# boilerplate.net
KiCad netlist of a schematic drawn in EAGLE
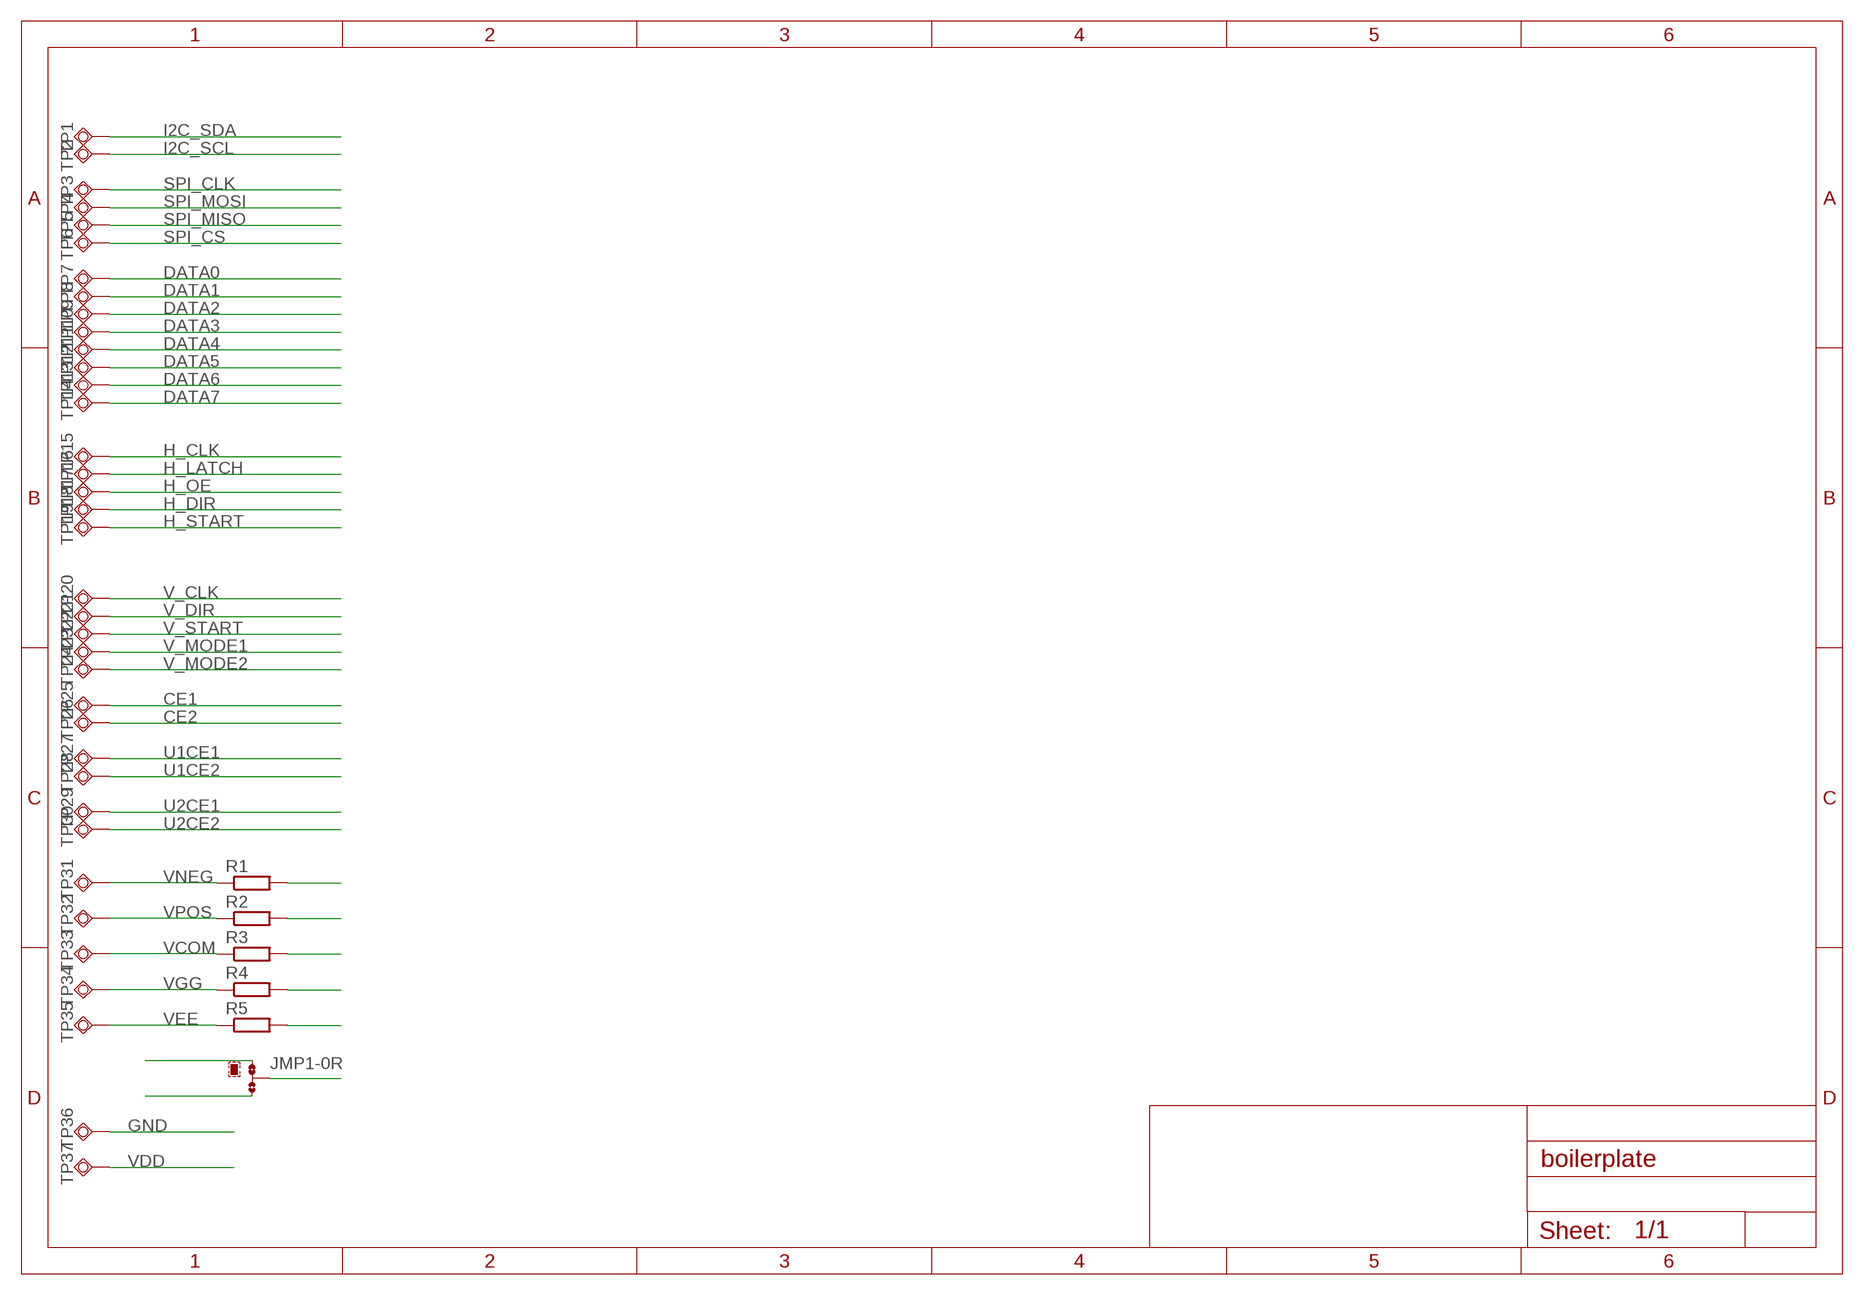
[diagram p0: schematic, sheet 1]

(export (version "E")
  (design (tool "Eeschema 10.0.6"))
  (components
    (comp (ref "JMP1")
      (value "0R-JUMPA")
      (footprint "eagle-import:A0R-JMP")
      (libsource (lib "eagle-import") (part "0R-JUMPA"))
    )
    (comp (ref "R1")
      (value "R-EU_R0805")
      (footprint "eagle-import:R0805")
      (libsource (lib "eagle-import") (part "R-EU_R0805"))
    )
    (comp (ref "R2")
      (value "R-EU_R0805")
      (footprint "eagle-import:R0805")
      (libsource (lib "eagle-import") (part "R-EU_R0805"))
    )
    (comp (ref "R3")
      (value "R-EU_R0805")
      (footprint "eagle-import:R0805")
      (libsource (lib "eagle-import") (part "R-EU_R0805"))
    )
    (comp (ref "R4")
      (value "R-EU_R0805")
      (footprint "eagle-import:R0805")
      (libsource (lib "eagle-import") (part "R-EU_R0805"))
    )
    (comp (ref "R5")
      (value "R-EU_R0805")
      (footprint "eagle-import:R0805")
      (libsource (lib "eagle-import") (part "R-EU_R0805"))
    )
    (comp (ref "TP1")
      (value "TESTPAD0.6")
      (footprint "eagle-import:VIA0.6")
      (libsource (lib "eagle-import") (part "TESTPAD0.6"))
    )
    (comp (ref "TP2")
      (value "TESTPAD0.6")
      (footprint "eagle-import:VIA0.6")
      (libsource (lib "eagle-import") (part "TESTPAD0.6"))
    )
    (comp (ref "TP3")
      (value "TESTPAD0.6")
      (footprint "eagle-import:VIA0.6")
      (libsource (lib "eagle-import") (part "TESTPAD0.6"))
    )
    (comp (ref "TP4")
      (value "TESTPAD0.6")
      (footprint "eagle-import:VIA0.6")
      (libsource (lib "eagle-import") (part "TESTPAD0.6"))
    )
    (comp (ref "TP5")
      (value "TESTPAD0.6")
      (footprint "eagle-import:VIA0.6")
      (libsource (lib "eagle-import") (part "TESTPAD0.6"))
    )
    (comp (ref "TP6")
      (value "TESTPAD0.6")
      (footprint "eagle-import:VIA0.6")
      (libsource (lib "eagle-import") (part "TESTPAD0.6"))
    )
    (comp (ref "TP7")
      (value "TESTPAD0.6")
      (footprint "eagle-import:VIA0.6")
      (libsource (lib "eagle-import") (part "TESTPAD0.6"))
    )
    (comp (ref "TP8")
      (value "TESTPAD0.6")
      (footprint "eagle-import:VIA0.6")
      (libsource (lib "eagle-import") (part "TESTPAD0.6"))
    )
    (comp (ref "TP9")
      (value "TESTPAD0.6")
      (footprint "eagle-import:VIA0.6")
      (libsource (lib "eagle-import") (part "TESTPAD0.6"))
    )
    (comp (ref "TP10")
      (value "TESTPAD0.6")
      (footprint "eagle-import:VIA0.6")
      (libsource (lib "eagle-import") (part "TESTPAD0.6"))
    )
    (comp (ref "TP11")
      (value "TESTPAD0.6")
      (footprint "eagle-import:VIA0.6")
      (libsource (lib "eagle-import") (part "TESTPAD0.6"))
    )
    (comp (ref "TP12")
      (value "TESTPAD0.6")
      (footprint "eagle-import:VIA0.6")
      (libsource (lib "eagle-import") (part "TESTPAD0.6"))
    )
    (comp (ref "TP13")
      (value "TESTPAD0.6")
      (footprint "eagle-import:VIA0.6")
      (libsource (lib "eagle-import") (part "TESTPAD0.6"))
    )
    (comp (ref "TP14")
      (value "TESTPAD0.6")
      (footprint "eagle-import:VIA0.6")
      (libsource (lib "eagle-import") (part "TESTPAD0.6"))
    )
    (comp (ref "TP15")
      (value "TESTPAD0.6")
      (footprint "eagle-import:VIA0.6")
      (libsource (lib "eagle-import") (part "TESTPAD0.6"))
    )
    (comp (ref "TP16")
      (value "TESTPAD0.6")
      (footprint "eagle-import:VIA0.6")
      (libsource (lib "eagle-import") (part "TESTPAD0.6"))
    )
    (comp (ref "TP17")
      (value "TESTPAD0.6")
      (footprint "eagle-import:VIA0.6")
      (libsource (lib "eagle-import") (part "TESTPAD0.6"))
    )
    (comp (ref "TP18")
      (value "TESTPAD0.6")
      (footprint "eagle-import:VIA0.6")
      (libsource (lib "eagle-import") (part "TESTPAD0.6"))
    )
    (comp (ref "TP19")
      (value "TESTPAD0.6")
      (footprint "eagle-import:VIA0.6")
      (libsource (lib "eagle-import") (part "TESTPAD0.6"))
    )
    (comp (ref "TP20")
      (value "TESTPAD0.6")
      (footprint "eagle-import:VIA0.6")
      (libsource (lib "eagle-import") (part "TESTPAD0.6"))
    )
    (comp (ref "TP21")
      (value "TESTPAD0.6")
      (footprint "eagle-import:VIA0.6")
      (libsource (lib "eagle-import") (part "TESTPAD0.6"))
    )
    (comp (ref "TP22")
      (value "TESTPAD0.6")
      (footprint "eagle-import:VIA0.6")
      (libsource (lib "eagle-import") (part "TESTPAD0.6"))
    )
    (comp (ref "TP23")
      (value "TESTPAD0.6")
      (footprint "eagle-import:VIA0.6")
      (libsource (lib "eagle-import") (part "TESTPAD0.6"))
    )
    (comp (ref "TP24")
      (value "TESTPAD0.6")
      (footprint "eagle-import:VIA0.6")
      (libsource (lib "eagle-import") (part "TESTPAD0.6"))
    )
    (comp (ref "TP25")
      (value "TESTPAD0.6")
      (footprint "eagle-import:VIA0.6")
      (libsource (lib "eagle-import") (part "TESTPAD0.6"))
    )
    (comp (ref "TP26")
      (value "TESTPAD0.6")
      (footprint "eagle-import:VIA0.6")
      (libsource (lib "eagle-import") (part "TESTPAD0.6"))
    )
    (comp (ref "TP27")
      (value "TESTPAD0.6")
      (footprint "eagle-import:VIA0.6")
      (libsource (lib "eagle-import") (part "TESTPAD0.6"))
    )
    (comp (ref "TP28")
      (value "TESTPAD0.6")
      (footprint "eagle-import:VIA0.6")
      (libsource (lib "eagle-import") (part "TESTPAD0.6"))
    )
    (comp (ref "TP29")
      (value "TESTPAD0.6")
      (footprint "eagle-import:VIA0.6")
      (libsource (lib "eagle-import") (part "TESTPAD0.6"))
    )
    (comp (ref "TP30")
      (value "TESTPAD0.6")
      (footprint "eagle-import:VIA0.6")
      (libsource (lib "eagle-import") (part "TESTPAD0.6"))
    )
    (comp (ref "TP31")
      (value "TESTPAD0.6")
      (footprint "eagle-import:VIA0.6")
      (libsource (lib "eagle-import") (part "TESTPAD0.6"))
    )
    (comp (ref "TP32")
      (value "TESTPAD0.6")
      (footprint "eagle-import:VIA0.6")
      (libsource (lib "eagle-import") (part "TESTPAD0.6"))
    )
    (comp (ref "TP33")
      (value "TESTPAD0.6")
      (footprint "eagle-import:VIA0.6")
      (libsource (lib "eagle-import") (part "TESTPAD0.6"))
    )
    (comp (ref "TP34")
      (value "TESTPAD0.6")
      (footprint "eagle-import:VIA0.6")
      (libsource (lib "eagle-import") (part "TESTPAD0.6"))
    )
    (comp (ref "TP35")
      (value "TESTPAD0.6")
      (footprint "eagle-import:VIA0.6")
      (libsource (lib "eagle-import") (part "TESTPAD0.6"))
    )
    (comp (ref "TP36")
      (value "TESTPAD0.6")
      (footprint "eagle-import:VIA0.6")
      (libsource (lib "eagle-import") (part "TESTPAD0.6"))
    )
    (comp (ref "TP37")
      (value "TESTPAD0.6")
      (footprint "eagle-import:VIA0.6")
      (libsource (lib "eagle-import") (part "TESTPAD0.6"))
    )
  )
  (nets
    (net (code "1") (name "/CE1") (class "Default")
      (node (ref "TP25") (pin "P$1") (pinfunction "TP_P$1") (pintype "input"))
    )
    (net (code "2") (name "/CE2") (class "Default")
      (node (ref "TP26") (pin "P$1") (pinfunction "TP_P$1") (pintype "input"))
    )
    (net (code "3") (name "/DATA0") (class "Default")
      (node (ref "TP7") (pin "P$1") (pinfunction "TP_P$1") (pintype "input"))
    )
    (net (code "4") (name "/DATA1") (class "Default")
      (node (ref "TP8") (pin "P$1") (pinfunction "TP_P$1") (pintype "input"))
    )
    (net (code "5") (name "/DATA2") (class "Default")
      (node (ref "TP9") (pin "P$1") (pinfunction "TP_P$1") (pintype "input"))
    )
    (net (code "6") (name "/DATA3") (class "Default")
      (node (ref "TP10") (pin "P$1") (pinfunction "TP_P$1") (pintype "input"))
    )
    (net (code "7") (name "/DATA4") (class "Default")
      (node (ref "TP11") (pin "P$1") (pinfunction "TP_P$1") (pintype "input"))
    )
    (net (code "8") (name "/DATA5") (class "Default")
      (node (ref "TP12") (pin "P$1") (pinfunction "TP_P$1") (pintype "input"))
    )
    (net (code "9") (name "/DATA6") (class "Default")
      (node (ref "TP13") (pin "P$1") (pinfunction "TP_P$1") (pintype "input"))
    )
    (net (code "10") (name "/DATA7") (class "Default")
      (node (ref "TP14") (pin "P$1") (pinfunction "TP_P$1") (pintype "input"))
    )
    (net (code "11") (name "/GND") (class "Default")
      (node (ref "TP36") (pin "P$1") (pinfunction "TP_P$1") (pintype "input"))
    )
    (net (code "12") (name "/H_CLK") (class "Default")
      (node (ref "TP15") (pin "P$1") (pinfunction "TP_P$1") (pintype "input"))
    )
    (net (code "13") (name "/H_DIR") (class "Default")
      (node (ref "TP18") (pin "P$1") (pinfunction "TP_P$1") (pintype "input"))
    )
    (net (code "14") (name "/H_LATCH") (class "Default")
      (node (ref "TP16") (pin "P$1") (pinfunction "TP_P$1") (pintype "input"))
    )
    (net (code "15") (name "/H_OE") (class "Default")
      (node (ref "TP17") (pin "P$1") (pinfunction "TP_P$1") (pintype "input"))
    )
    (net (code "16") (name "/H_START") (class "Default")
      (node (ref "TP19") (pin "P$1") (pinfunction "TP_P$1") (pintype "input"))
    )
    (net (code "17") (name "/I2C_SCL") (class "Default")
      (node (ref "TP2") (pin "P$1") (pinfunction "TP_P$1") (pintype "input"))
    )
    (net (code "18") (name "/I2C_SDA") (class "Default")
      (node (ref "TP1") (pin "P$1") (pinfunction "TP_P$1") (pintype "input"))
    )
    (net (code "19") (name "/SPI_CLK") (class "Default")
      (node (ref "TP3") (pin "P$1") (pinfunction "TP_P$1") (pintype "input"))
    )
    (net (code "20") (name "/SPI_CS") (class "Default")
      (node (ref "TP6") (pin "P$1") (pinfunction "TP_P$1") (pintype "input"))
    )
    (net (code "21") (name "/SPI_MISO") (class "Default")
      (node (ref "TP5") (pin "P$1") (pinfunction "TP_P$1") (pintype "input"))
    )
    (net (code "22") (name "/SPI_MOSI") (class "Default")
      (node (ref "TP4") (pin "P$1") (pinfunction "TP_P$1") (pintype "input"))
    )
    (net (code "23") (name "/U1CE1") (class "Default")
      (node (ref "TP27") (pin "P$1") (pinfunction "TP_P$1") (pintype "input"))
    )
    (net (code "24") (name "/U1CE2") (class "Default")
      (node (ref "TP28") (pin "P$1") (pinfunction "TP_P$1") (pintype "input"))
    )
    (net (code "25") (name "/U2CE1") (class "Default")
      (node (ref "TP29") (pin "P$1") (pinfunction "TP_P$1") (pintype "input"))
    )
    (net (code "26") (name "/U2CE2") (class "Default")
      (node (ref "TP30") (pin "P$1") (pinfunction "TP_P$1") (pintype "input"))
    )
    (net (code "27") (name "/VCOM") (class "Default")
      (node (ref "R3") (pin "1") (pinfunction "1_1") (pintype "passive"))
      (node (ref "TP33") (pin "P$1") (pinfunction "TP_P$1") (pintype "input"))
    )
    (net (code "28") (name "/VDD") (class "Default")
      (node (ref "TP37") (pin "P$1") (pinfunction "TP_P$1") (pintype "input"))
    )
    (net (code "29") (name "/VEE") (class "Default")
      (node (ref "R5") (pin "1") (pinfunction "1_1") (pintype "passive"))
      (node (ref "TP35") (pin "P$1") (pinfunction "TP_P$1") (pintype "input"))
    )
    (net (code "30") (name "/VGG") (class "Default")
      (node (ref "R4") (pin "1") (pinfunction "1_1") (pintype "passive"))
      (node (ref "TP34") (pin "P$1") (pinfunction "TP_P$1") (pintype "input"))
    )
    (net (code "31") (name "/VNEG") (class "Default")
      (node (ref "R1") (pin "1") (pinfunction "1_1") (pintype "passive"))
      (node (ref "TP31") (pin "P$1") (pinfunction "TP_P$1") (pintype "input"))
    )
    (net (code "32") (name "/VPOS") (class "Default")
      (node (ref "R2") (pin "1") (pinfunction "1_1") (pintype "passive"))
      (node (ref "TP32") (pin "P$1") (pinfunction "TP_P$1") (pintype "input"))
    )
    (net (code "33") (name "/V_CLK") (class "Default")
      (node (ref "TP20") (pin "P$1") (pinfunction "TP_P$1") (pintype "input"))
    )
    (net (code "34") (name "/V_DIR") (class "Default")
      (node (ref "TP21") (pin "P$1") (pinfunction "TP_P$1") (pintype "input"))
    )
    (net (code "35") (name "/V_MODE1") (class "Default")
      (node (ref "TP23") (pin "P$1") (pinfunction "TP_P$1") (pintype "input"))
    )
    (net (code "36") (name "/V_MODE2") (class "Default")
      (node (ref "TP24") (pin "P$1") (pinfunction "TP_P$1") (pintype "input"))
    )
    (net (code "37") (name "/V_START") (class "Default")
      (node (ref "TP22") (pin "P$1") (pinfunction "TP_P$1") (pintype "input"))
    )
    (net (code "38") (name "unconnected-(JMP1-Pad1)") (class "Default")
      (node (ref "JMP1") (pin "1") (pinfunction "1_1") (pintype "passive"))
    )
    (net (code "39") (name "unconnected-(JMP1-Pad2)") (class "Default")
      (node (ref "JMP1") (pin "2") (pinfunction "2_2") (pintype "passive"))
    )
    (net (code "40") (name "unconnected-(JMP1-Pad3)") (class "Default")
      (node (ref "JMP1") (pin "3") (pinfunction "3_3") (pintype "passive"))
    )
    (net (code "41") (name "unconnected-(R1-Pad2)") (class "Default")
      (node (ref "R1") (pin "2") (pinfunction "2_2") (pintype "passive"))
    )
    (net (code "42") (name "unconnected-(R2-Pad2)") (class "Default")
      (node (ref "R2") (pin "2") (pinfunction "2_2") (pintype "passive"))
    )
    (net (code "43") (name "unconnected-(R3-Pad2)") (class "Default")
      (node (ref "R3") (pin "2") (pinfunction "2_2") (pintype "passive"))
    )
    (net (code "44") (name "unconnected-(R4-Pad2)") (class "Default")
      (node (ref "R4") (pin "2") (pinfunction "2_2") (pintype "passive"))
    )
    (net (code "45") (name "unconnected-(R5-Pad2)") (class "Default")
      (node (ref "R5") (pin "2") (pinfunction "2_2") (pintype "passive"))
    )
  )
)
